# interceptor.net
KiCad netlist of a schematic drawn in EAGLE
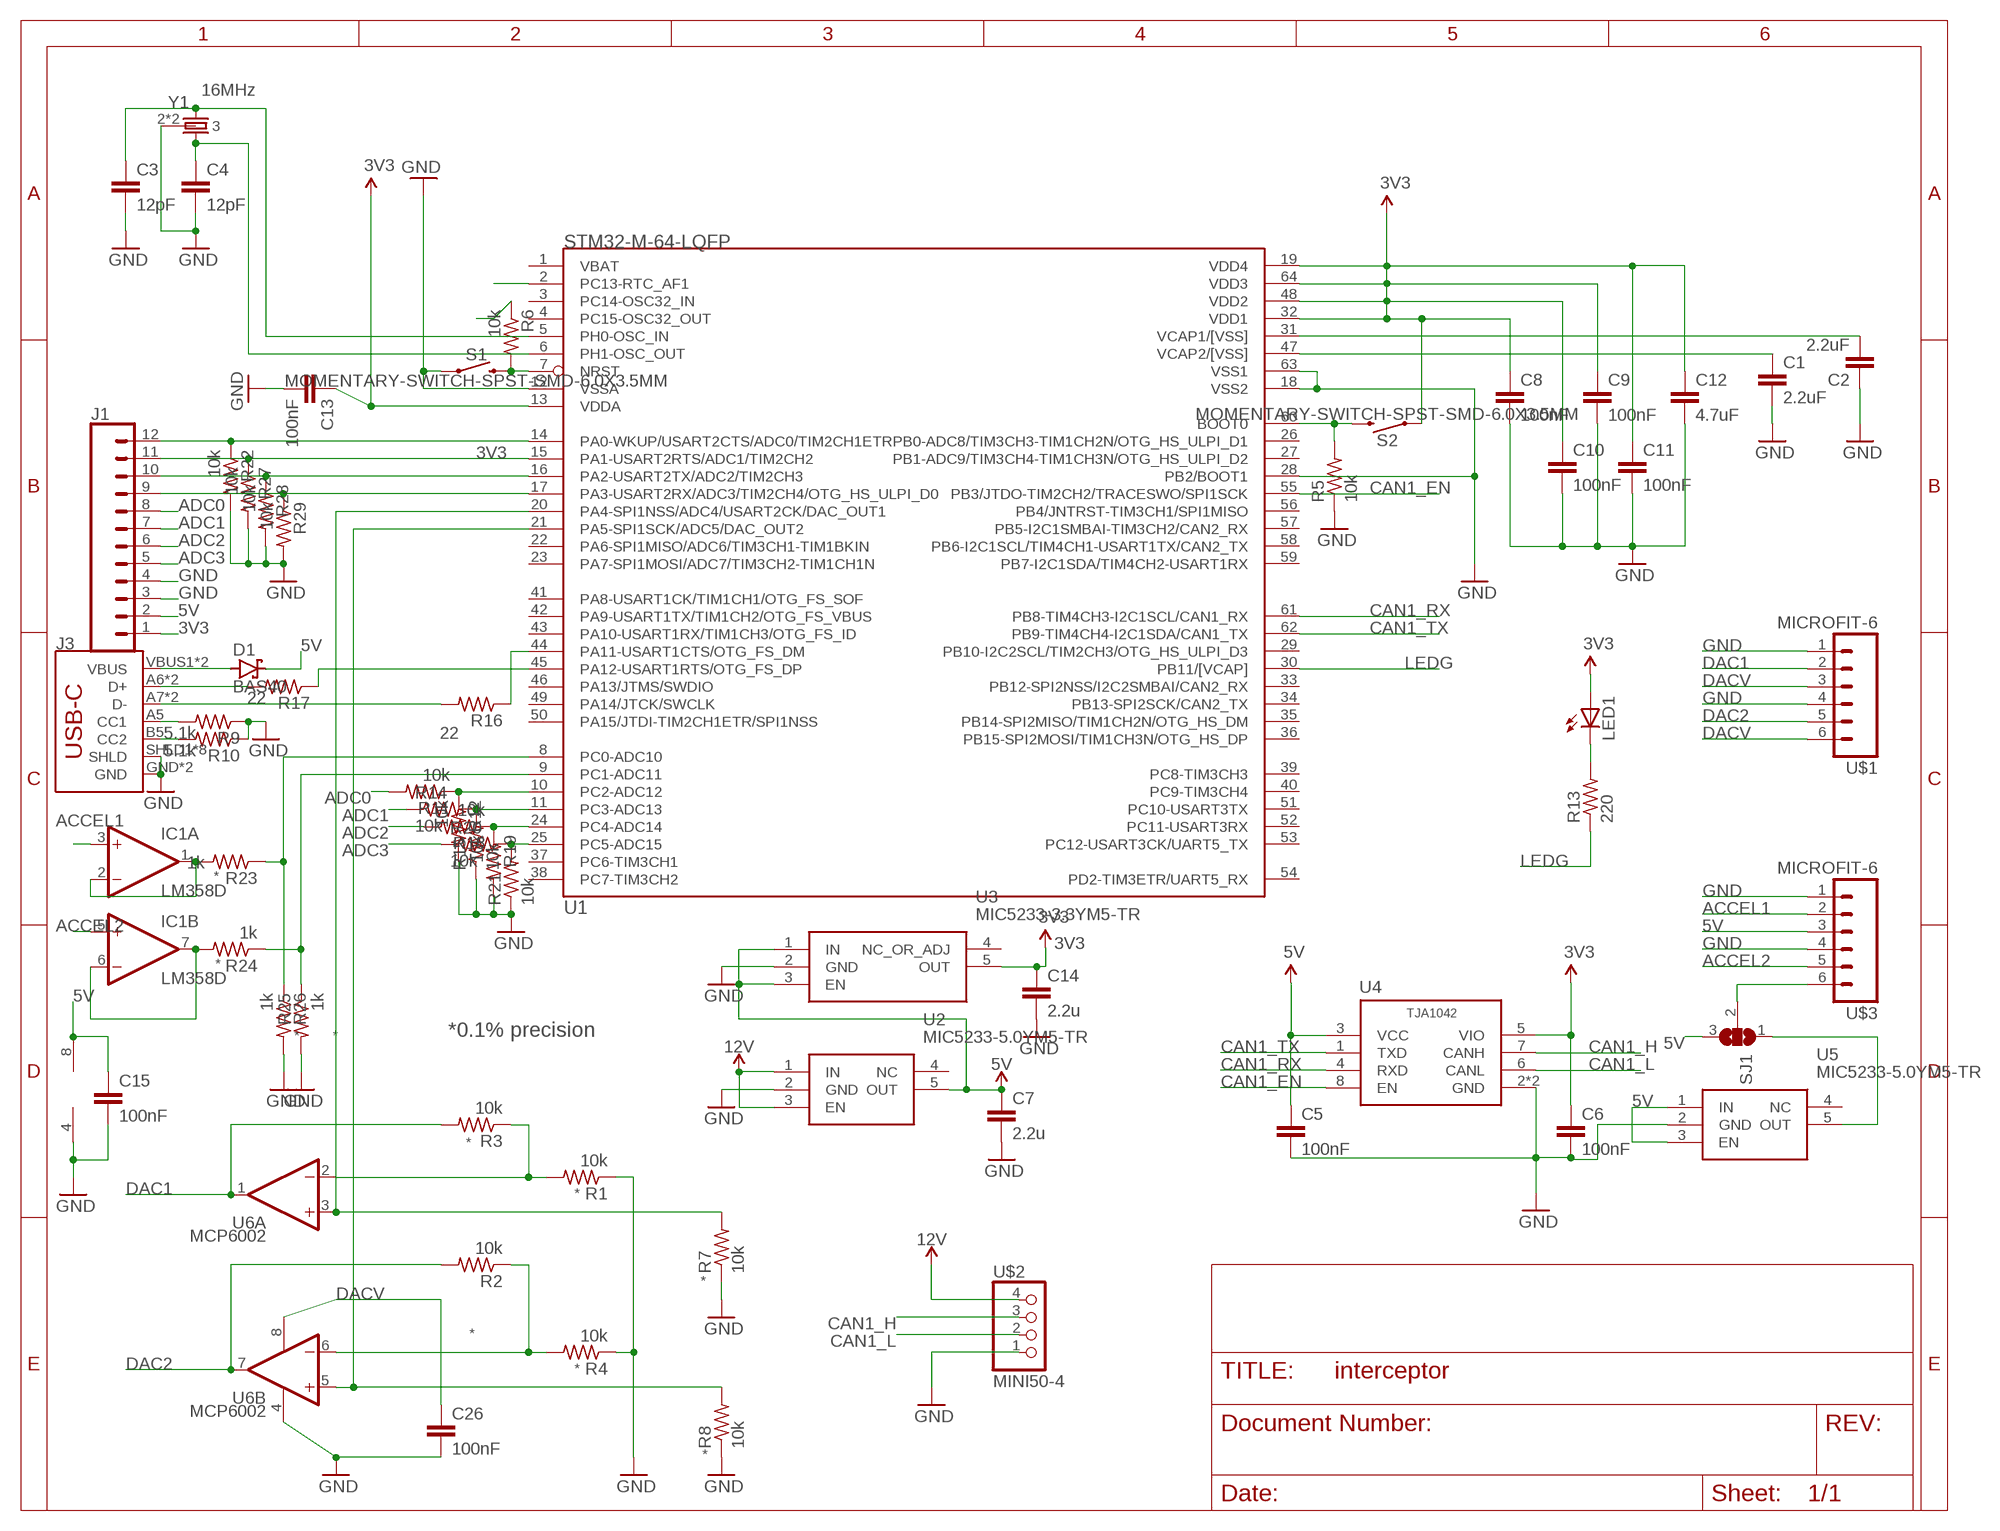
[diagram p0: schematic, sheet 1]

(export (version "E")
  (design (tool "Eeschema 10.0.6"))
  (components
    (comp (ref "C1")
      (value "2.2uF")
      (footprint "eagle-import:0603-C")
      (libsource (lib "eagle-import") (part "C0603"))
    )
    (comp (ref "C2")
      (value "2.2uF")
      (footprint "eagle-import:0603-C")
      (libsource (lib "eagle-import") (part "C0603"))
    )
    (comp (ref "C3")
      (value "12pF")
      (footprint "eagle-import:0603-C")
      (libsource (lib "eagle-import") (part "C0603"))
    )
    (comp (ref "C4")
      (value "12pF")
      (footprint "eagle-import:0603-C")
      (libsource (lib "eagle-import") (part "C0603"))
    )
    (comp (ref "C5")
      (value "100nF")
      (footprint "eagle-import:0603-C")
      (libsource (lib "eagle-import") (part "C0603"))
    )
    (comp (ref "C6")
      (value "100nF")
      (footprint "eagle-import:0603-C")
      (libsource (lib "eagle-import") (part "C0603"))
    )
    (comp (ref "C7")
      (value "2.2u")
      (footprint "eagle-import:C0603")
      (libsource (lib "eagle-import") (part "C-EUC0603"))
    )
    (comp (ref "C8")
      (value "100nF")
      (footprint "eagle-import:0603-C")
      (libsource (lib "eagle-import") (part "C0603"))
    )
    (comp (ref "C9")
      (value "100nF")
      (footprint "eagle-import:0603-C")
      (libsource (lib "eagle-import") (part "C0603"))
    )
    (comp (ref "C10")
      (value "100nF")
      (footprint "eagle-import:0603-C")
      (libsource (lib "eagle-import") (part "C0603"))
    )
    (comp (ref "C11")
      (value "100nF")
      (footprint "eagle-import:0603-C")
      (libsource (lib "eagle-import") (part "C0603"))
    )
    (comp (ref "C12")
      (value "4.7uF")
      (footprint "eagle-import:0603-C")
      (libsource (lib "eagle-import") (part "C0603"))
    )
    (comp (ref "C13")
      (value "100nF")
      (footprint "eagle-import:0603-C")
      (libsource (lib "eagle-import") (part "C0603"))
    )
    (comp (ref "C14")
      (value "2.2u")
      (footprint "eagle-import:C0603")
      (libsource (lib "eagle-import") (part "C-EUC0603"))
    )
    (comp (ref "C15")
      (value "100nF")
      (footprint "eagle-import:0603-C")
      (libsource (lib "eagle-import") (part "C0603"))
    )
    (comp (ref "C26")
      (value "100nF")
      (footprint "eagle-import:0603-C")
      (libsource (lib "eagle-import") (part "C0603"))
    )
    (comp (ref "D1")
      (value "BAS40")
      (footprint "eagle-import:SOT23")
      (libsource (lib "eagle-import") (part "BAS40"))
    )
    (comp (ref "IC1")
      (value "LM358D")
      (footprint "eagle-import:SO08")
      (libsource (lib "eagle-import") (part "LM358D"))
    )
    (comp (ref "J1")
      (value "CONN_12")
      (footprint "eagle-import:1X12")
      (libsource (lib "eagle-import") (part "CONN_12"))
    )
    (comp (ref "J3")
      (value "USB-C-BREAKOUT_SPARKFUN-CONNECTORS_USB_C16PIN")
      (footprint "eagle-import:USB-C-BREAKOUT_SPARKFUN-CONNECTORS_USB-C-16P")
      (libsource (lib "eagle-import") (part "USB-C-BREAKOUT_SPARKFUN-CONNECTORS_USB_C16PIN"))
    )
    (comp (ref "LED1")
      (value "LEDCHIPLED_0805")
      (footprint "eagle-import:CHIPLED_0805")
      (libsource (lib "eagle-import") (part "LEDCHIPLED_0805"))
    )
    (comp (ref "R1")
      (value "10k")
      (footprint "eagle-import:0402-R")
      (libsource (lib "eagle-import") (part "R0402"))
    )
    (comp (ref "R2")
      (value "10k")
      (footprint "eagle-import:0402-R")
      (libsource (lib "eagle-import") (part "R0402"))
    )
    (comp (ref "R3")
      (value "10k")
      (footprint "eagle-import:0402-R")
      (libsource (lib "eagle-import") (part "R0402"))
    )
    (comp (ref "R4")
      (value "10k")
      (footprint "eagle-import:0402-R")
      (libsource (lib "eagle-import") (part "R0402"))
    )
    (comp (ref "R5")
      (value "10k")
      (footprint "eagle-import:0402-R")
      (libsource (lib "eagle-import") (part "R0402"))
    )
    (comp (ref "R6")
      (value "10k")
      (footprint "eagle-import:0402-R")
      (libsource (lib "eagle-import") (part "R0402"))
    )
    (comp (ref "R7")
      (value "10k")
      (footprint "eagle-import:0402-R")
      (libsource (lib "eagle-import") (part "R0402"))
    )
    (comp (ref "R8")
      (value "10k")
      (footprint "eagle-import:0402-R")
      (libsource (lib "eagle-import") (part "R0402"))
    )
    (comp (ref "R9")
      (value "5.1k")
      (footprint "eagle-import:0402-R")
      (libsource (lib "eagle-import") (part "R0402"))
    )
    (comp (ref "R10")
      (value "5.1k")
      (footprint "eagle-import:0402-R")
      (libsource (lib "eagle-import") (part "R0402"))
    )
    (comp (ref "R11")
      (value "10k")
      (footprint "eagle-import:0402-R")
      (libsource (lib "eagle-import") (part "R0402"))
    )
    (comp (ref "R12")
      (value "10k")
      (footprint "eagle-import:0402-R")
      (libsource (lib "eagle-import") (part "R0402"))
    )
    (comp (ref "R13")
      (value "220")
      (footprint "eagle-import:0402-R")
      (libsource (lib "eagle-import") (part "R0402"))
    )
    (comp (ref "R14")
      (value "10k")
      (footprint "eagle-import:0402-R")
      (libsource (lib "eagle-import") (part "R0402"))
    )
    (comp (ref "R15")
      (value "10k")
      (footprint "eagle-import:0402-R")
      (libsource (lib "eagle-import") (part "R0402"))
    )
    (comp (ref "R16")
      (value "22")
      (footprint "eagle-import:0402-R")
      (libsource (lib "eagle-import") (part "R0402"))
    )
    (comp (ref "R17")
      (value "22")
      (footprint "eagle-import:0402-R")
      (libsource (lib "eagle-import") (part "R0402"))
    )
    (comp (ref "R18")
      (value "10k")
      (footprint "eagle-import:0402-R")
      (libsource (lib "eagle-import") (part "R0402"))
    )
    (comp (ref "R19")
      (value "10k")
      (footprint "eagle-import:0402-R")
      (libsource (lib "eagle-import") (part "R0402"))
    )
    (comp (ref "R20")
      (value "10k")
      (footprint "eagle-import:0402-R")
      (libsource (lib "eagle-import") (part "R0402"))
    )
    (comp (ref "R21")
      (value "10k")
      (footprint "eagle-import:0402-R")
      (libsource (lib "eagle-import") (part "R0402"))
    )
    (comp (ref "R22")
      (value "10k")
      (footprint "eagle-import:0402-R")
      (libsource (lib "eagle-import") (part "R0402"))
    )
    (comp (ref "R23")
      (value "1k")
      (footprint "eagle-import:0402-R")
      (libsource (lib "eagle-import") (part "R0402"))
    )
    (comp (ref "R24")
      (value "1k")
      (footprint "eagle-import:0402-R")
      (libsource (lib "eagle-import") (part "R0402"))
    )
    (comp (ref "R25")
      (value "1k")
      (footprint "eagle-import:0402-R")
      (libsource (lib "eagle-import") (part "R0402"))
    )
    (comp (ref "R26")
      (value "1k")
      (footprint "eagle-import:0402-R")
      (libsource (lib "eagle-import") (part "R0402"))
    )
    (comp (ref "R27")
      (value "10k")
      (footprint "eagle-import:0402-R")
      (libsource (lib "eagle-import") (part "R0402"))
    )
    (comp (ref "R28")
      (value "10k")
      (footprint "eagle-import:0402-R")
      (libsource (lib "eagle-import") (part "R0402"))
    )
    (comp (ref "R29")
      (value "10k")
      (footprint "eagle-import:0402-R")
      (libsource (lib "eagle-import") (part "R0402"))
    )
    (comp (ref "S1")
      (value "MOMENTARY-SWITCH-SPST-SMD-6.0X3.5MM")
      (footprint "eagle-import:TACTILE_SWITCH_SMD_6.0X3.5MM")
      (libsource (lib "eagle-import") (part "MOMENTARY-SWITCH-SPST-SMD-6.0X3.5MM"))
    )
    (comp (ref "S2")
      (value "MOMENTARY-SWITCH-SPST-SMD-6.0X3.5MM")
      (footprint "eagle-import:TACTILE_SWITCH_SMD_6.0X3.5MM")
      (libsource (lib "eagle-import") (part "MOMENTARY-SWITCH-SPST-SMD-6.0X3.5MM"))
    )
    (comp (ref "SJ1")
      (value "SJ2W")
      (footprint "eagle-import:SJ_2")
      (libsource (lib "eagle-import") (part "SJ2W"))
    )
    (comp (ref "U$1")
      (value "MICROFIT-6")
      (footprint "eagle-import:MICROFIT-6")
      (libsource (lib "eagle-import") (part "MICROFIT-6"))
    )
    (comp (ref "U$2")
      (value "MINI50-4")
      (footprint "eagle-import:MINI50")
      (libsource (lib "eagle-import") (part "MINI50-4"))
    )
    (comp (ref "U$3")
      (value "MICROFIT-6")
      (footprint "eagle-import:MICROFIT-6")
      (libsource (lib "eagle-import") (part "MICROFIT-6"))
    )
    (comp (ref "U1")
      (value "STM32-M-64-LQFP")
      (footprint "eagle-import:LQFP64")
      (libsource (lib "eagle-import") (part "STM32-M-64-LQFP"))
    )
    (comp (ref "U2")
      (value "MIC5233-5.0YM5-TR")
      (footprint "eagle-import:SOT95P280X145-5N")
      (fields (field (name "MOUSER_PART_NUMBER") "998-MIC5233-5.0YM5TR"))
      (libsource (lib "eagle-import") (part "MIC5233-5.0YM5-TR"))
    )
    (comp (ref "U3")
      (value "MIC5233-3.3YM5-TR")
      (footprint "eagle-import:SOT95P280X145-5N")
      (fields (field (name "MOUSER_PART_NUMBER") "998-MIC5233-3.3YM5TR"))
      (libsource (lib "eagle-import") (part "MIC5233-3.3YM5-TR"))
    )
    (comp (ref "U4")
      (value "TJA1042HVSON")
      (footprint "eagle-import:HVSON8")
      (libsource (lib "eagle-import") (part "TJA1042HVSON"))
    )
    (comp (ref "U5")
      (value "MIC5233-5.0YM5-TR")
      (footprint "eagle-import:SOT95P280X145-5N")
      (fields (field (name "MOUSER_PART_NUMBER") "998-MIC5233-5.0YM5TR"))
      (libsource (lib "eagle-import") (part "MIC5233-5.0YM5-TR"))
    )
    (comp (ref "U6")
      (value "MCP6002")
      (footprint "eagle-import:SO08")
      (libsource (lib "eagle-import") (part "LM358D"))
    )
    (comp (ref "Y1")
      (value "16MHz")
      (footprint "eagle-import:XTAL-3.2X2.5")
      (libsource (lib "eagle-import") (part "CRYSTAL-3.2X2.54-PIN"))
    )
  )
  (nets
    (net (code "1") (name "/ACCEL1") (class "Default")
      (node (ref "IC1") (pin "3") (pinfunction "+IN_3") (pintype "input"))
      (node (ref "U$3") (pin "2") (pinfunction "2_2") (pintype "passive"))
    )
    (net (code "2") (name "/ACCEL2") (class "Default")
      (node (ref "IC1") (pin "5") (pinfunction "+IN_5") (pintype "input"))
      (node (ref "U$3") (pin "5") (pinfunction "5_5") (pintype "passive"))
    )
    (net (code "3") (name "/ADC0") (class "Default")
      (node (ref "J1") (pin "8") (pinfunction "8_8") (pintype "passive"))
      (node (ref "R11") (pin "2") (pinfunction "2_2") (pintype "passive"))
    )
    (net (code "4") (name "/ADC1") (class "Default")
      (node (ref "J1") (pin "7") (pinfunction "7_7") (pintype "passive"))
      (node (ref "R14") (pin "1") (pinfunction "1_1") (pintype "passive"))
    )
    (net (code "5") (name "/ADC2") (class "Default")
      (node (ref "J1") (pin "6") (pinfunction "6_6") (pintype "passive"))
      (node (ref "R18") (pin "2") (pinfunction "2_2") (pintype "passive"))
    )
    (net (code "6") (name "/ADC3") (class "Default")
      (node (ref "J1") (pin "5") (pinfunction "5_5") (pintype "passive"))
      (node (ref "R20") (pin "1") (pinfunction "1_1") (pintype "passive"))
    )
    (net (code "7") (name "/CAN1_EN") (class "Default")
      (node (ref "U1") (pin "55") (pinfunction "PB3/JTDO-TIM2CH2/TRACESWO/SPI1SCK_55") (pintype "bidirectional"))
      (node (ref "U4") (pin "8") (pinfunction "EN_8") (pintype "bidirectional"))
    )
    (net (code "8") (name "/CAN1_H") (class "Default")
      (node (ref "U$2") (pin "3") (pinfunction "2_3") (pintype "passive"))
      (node (ref "U4") (pin "7") (pinfunction "CANH_7") (pintype "bidirectional"))
    )
    (net (code "9") (name "/CAN1_L") (class "Default")
      (node (ref "U$2") (pin "2") (pinfunction "3_2") (pintype "passive"))
      (node (ref "U4") (pin "6") (pinfunction "CANL_6") (pintype "bidirectional"))
    )
    (net (code "10") (name "/CAN1_RX") (class "Default")
      (node (ref "U1") (pin "61") (pinfunction "PB8-TIM4CH3-I2C1SCL/CAN1_RX_61") (pintype "bidirectional"))
      (node (ref "U4") (pin "4") (pinfunction "RXD_4") (pintype "bidirectional"))
    )
    (net (code "11") (name "/CAN1_TX") (class "Default")
      (node (ref "U1") (pin "62") (pinfunction "PB9-TIM4CH4-I2C1SDA/CAN1_TX_62") (pintype "bidirectional"))
      (node (ref "U4") (pin "1") (pinfunction "TXD_1") (pintype "bidirectional"))
    )
    (net (code "12") (name "/DAC1") (class "Default")
      (node (ref "R3") (pin "2") (pinfunction "2_2") (pintype "passive"))
      (node (ref "U$1") (pin "2") (pinfunction "2_2") (pintype "passive"))
      (node (ref "U6") (pin "1") (pinfunction "OUT_1") (pintype "output"))
    )
    (net (code "13") (name "/DAC2") (class "Default")
      (node (ref "R2") (pin "2") (pinfunction "2_2") (pintype "passive"))
      (node (ref "U$1") (pin "5") (pinfunction "5_5") (pintype "passive"))
      (node (ref "U6") (pin "7") (pinfunction "OUT_7") (pintype "output"))
    )
    (net (code "14") (name "/DACV") (class "Default")
      (node (ref "C26") (pin "1") (pinfunction "1_1") (pintype "passive"))
      (node (ref "U$1") (pin "3") (pinfunction "3_3") (pintype "passive"))
      (node (ref "U$1") (pin "6") (pinfunction "6_6") (pintype "passive"))
      (node (ref "U6") (pin "8") (pinfunction "V+_8") (pintype "power_in"))
    )
    (net (code "15") (name "/LEDG") (class "Default")
      (node (ref "R13") (pin "1") (pinfunction "1_1") (pintype "passive"))
      (node (ref "U1") (pin "30") (pinfunction "PB11/[VCAP]_30") (pintype "bidirectional"))
    )
    (net (code "16") (name "/VBAT") (class "Default")
      (node (ref "U1") (pin "1") (pinfunction "VBAT_1") (pintype "power_in"))
    )
    (net (code "17") (name "3V3") (class "Default")
      (node (ref "C10") (pin "1") (pinfunction "1_1") (pintype "passive"))
      (node (ref "C11") (pin "1") (pinfunction "1_1") (pintype "passive"))
      (node (ref "C12") (pin "1") (pinfunction "1_1") (pintype "passive"))
      (node (ref "C13") (pin "1") (pinfunction "1_1") (pintype "passive"))
      (node (ref "C14") (pin "1") (pinfunction "1_1") (pintype "passive"))
      (node (ref "C6") (pin "1") (pinfunction "1_1") (pintype "passive"))
      (node (ref "C8") (pin "1") (pinfunction "1_1") (pintype "passive"))
      (node (ref "C9") (pin "1") (pinfunction "1_1") (pintype "passive"))
      (node (ref "J1") (pin "1") (pinfunction "1_1") (pintype "passive"))
      (node (ref "LED1") (pin "A") (pinfunction "A_A") (pintype "passive"))
      (node (ref "R6") (pin "1") (pinfunction "1_1") (pintype "passive"))
      (node (ref "S2") (pin "1") (pinfunction "1_1") (pintype "passive"))
      (node (ref "U1") (pin "13") (pinfunction "VDDA_13") (pintype "power_in"))
      (node (ref "U1") (pin "19") (pinfunction "VDD4_19") (pintype "bidirectional"))
      (node (ref "U1") (pin "32") (pinfunction "VDD1_32") (pintype "power_in"))
      (node (ref "U1") (pin "48") (pinfunction "VDD2_48") (pintype "power_in"))
      (node (ref "U1") (pin "64") (pinfunction "VDD3_64") (pintype "power_in"))
      (node (ref "U3") (pin "5") (pinfunction "OUT_5") (pintype "bidirectional"))
      (node (ref "U4") (pin "5") (pinfunction "VIO_5") (pintype "bidirectional"))
    )
    (net (code "18") (name "5V") (class "Default")
      (node (ref "C15") (pin "1") (pinfunction "1_1") (pintype "passive"))
      (node (ref "C5") (pin "1") (pinfunction "1_1") (pintype "passive"))
      (node (ref "C7") (pin "1") (pinfunction "1_1") (pintype "passive"))
      (node (ref "D1") (pin "3") (pinfunction "C_3") (pintype "passive"))
      (node (ref "IC1") (pin "8") (pinfunction "V+_8") (pintype "power_in"))
      (node (ref "J1") (pin "2") (pinfunction "2_2") (pintype "passive"))
      (node (ref "SJ1") (pin "3") (pinfunction "3_3") (pintype "passive"))
      (node (ref "U$3") (pin "3") (pinfunction "3_3") (pintype "passive"))
      (node (ref "U2") (pin "5") (pinfunction "OUT_5") (pintype "bidirectional"))
      (node (ref "U3") (pin "1") (pinfunction "IN_1") (pintype "bidirectional"))
      (node (ref "U3") (pin "3") (pinfunction "EN_3") (pintype "bidirectional"))
      (node (ref "U4") (pin "3") (pinfunction "VCC_3") (pintype "bidirectional"))
      (node (ref "U5") (pin "1") (pinfunction "IN_1") (pintype "bidirectional"))
      (node (ref "U5") (pin "3") (pinfunction "EN_3") (pintype "bidirectional"))
    )
    (net (code "19") (name "12V") (class "Default")
      (node (ref "U$2") (pin "4") (pinfunction "1_4") (pintype "passive"))
      (node (ref "U2") (pin "1") (pinfunction "IN_1") (pintype "bidirectional"))
      (node (ref "U2") (pin "3") (pinfunction "EN_3") (pintype "bidirectional"))
    )
    (net (code "20") (name "GND") (class "Default")
      (node (ref "C1") (pin "2") (pinfunction "2_2") (pintype "passive"))
      (node (ref "C10") (pin "2") (pinfunction "2_2") (pintype "passive"))
      (node (ref "C11") (pin "2") (pinfunction "2_2") (pintype "passive"))
      (node (ref "C12") (pin "2") (pinfunction "2_2") (pintype "passive"))
      (node (ref "C13") (pin "2") (pinfunction "2_2") (pintype "passive"))
      (node (ref "C14") (pin "2") (pinfunction "2_2") (pintype "passive"))
      (node (ref "C15") (pin "2") (pinfunction "2_2") (pintype "passive"))
      (node (ref "C2") (pin "1") (pinfunction "1_1") (pintype "passive"))
      (node (ref "C26") (pin "2") (pinfunction "2_2") (pintype "passive"))
      (node (ref "C3") (pin "2") (pinfunction "2_2") (pintype "passive"))
      (node (ref "C4") (pin "2") (pinfunction "2_2") (pintype "passive"))
      (node (ref "C5") (pin "2") (pinfunction "2_2") (pintype "passive"))
      (node (ref "C6") (pin "2") (pinfunction "2_2") (pintype "passive"))
      (node (ref "C7") (pin "2") (pinfunction "2_2") (pintype "passive"))
      (node (ref "C8") (pin "2") (pinfunction "2_2") (pintype "passive"))
      (node (ref "C9") (pin "2") (pinfunction "2_2") (pintype "passive"))
      (node (ref "IC1") (pin "4") (pinfunction "V-_4") (pintype "power_in"))
      (node (ref "J1") (pin "3") (pinfunction "3_3") (pintype "passive"))
      (node (ref "J1") (pin "4") (pinfunction "4_4") (pintype "passive"))
      (node (ref "J3") (pin "GND") (pinfunction "GND_GND") (pintype "bidirectional"))
      (node (ref "J3") (pin "GND2") (pinfunction "GND_GND2") (pintype "bidirectional"))
      (node (ref "J3") (pin "SHLD1") (pinfunction "SHLD_SHLD1") (pintype "bidirectional"))
      (node (ref "J3") (pin "SHLD2") (pinfunction "SHLD_SHLD2") (pintype "bidirectional"))
      (node (ref "J3") (pin "SHLD3") (pinfunction "SHLD_SHLD3") (pintype "bidirectional"))
      (node (ref "J3") (pin "SHLD4") (pinfunction "SHLD_SHLD4") (pintype "bidirectional"))
      (node (ref "J3") (pin "SHLD5") (pinfunction "SHLD_SHLD5") (pintype "bidirectional"))
      (node (ref "J3") (pin "SHLD6") (pinfunction "SHLD_SHLD6") (pintype "bidirectional"))
      (node (ref "J3") (pin "SHLD7") (pinfunction "SHLD_SHLD7") (pintype "bidirectional"))
      (node (ref "J3") (pin "SHLD8") (pinfunction "SHLD_SHLD8") (pintype "bidirectional"))
      (node (ref "R1") (pin "1") (pinfunction "1_1") (pintype "passive"))
      (node (ref "R10") (pin "1") (pinfunction "1_1") (pintype "passive"))
      (node (ref "R12") (pin "2") (pinfunction "2_2") (pintype "passive"))
      (node (ref "R15") (pin "1") (pinfunction "1_1") (pintype "passive"))
      (node (ref "R19") (pin "2") (pinfunction "2_2") (pintype "passive"))
      (node (ref "R21") (pin "1") (pinfunction "1_1") (pintype "passive"))
      (node (ref "R22") (pin "2") (pinfunction "2_2") (pintype "passive"))
      (node (ref "R25") (pin "2") (pinfunction "2_2") (pintype "passive"))
      (node (ref "R26") (pin "2") (pinfunction "2_2") (pintype "passive"))
      (node (ref "R27") (pin "2") (pinfunction "2_2") (pintype "passive"))
      (node (ref "R28") (pin "2") (pinfunction "2_2") (pintype "passive"))
      (node (ref "R29") (pin "2") (pinfunction "2_2") (pintype "passive"))
      (node (ref "R4") (pin "1") (pinfunction "1_1") (pintype "passive"))
      (node (ref "R5") (pin "1") (pinfunction "1_1") (pintype "passive"))
      (node (ref "R7") (pin "1") (pinfunction "1_1") (pintype "passive"))
      (node (ref "R8") (pin "1") (pinfunction "1_1") (pintype "passive"))
      (node (ref "R9") (pin "1") (pinfunction "1_1") (pintype "passive"))
      (node (ref "S1") (pin "1") (pinfunction "1_1") (pintype "passive"))
      (node (ref "U$1") (pin "1") (pinfunction "1_1") (pintype "passive"))
      (node (ref "U$1") (pin "4") (pinfunction "4_4") (pintype "passive"))
      (node (ref "U$2") (pin "1") (pinfunction "4_1") (pintype "passive"))
      (node (ref "U$3") (pin "1") (pinfunction "1_1") (pintype "passive"))
      (node (ref "U$3") (pin "4") (pinfunction "4_4") (pintype "passive"))
      (node (ref "U1") (pin "12") (pinfunction "VSSA_12") (pintype "power_in"))
      (node (ref "U1") (pin "18") (pinfunction "VSS2_18") (pintype "bidirectional"))
      (node (ref "U1") (pin "28") (pinfunction "PB2/BOOT1_28") (pintype "bidirectional"))
      (node (ref "U1") (pin "63") (pinfunction "VSS1_63") (pintype "power_in"))
      (node (ref "U2") (pin "2") (pinfunction "GND_2") (pintype "bidirectional"))
      (node (ref "U3") (pin "2") (pinfunction "GND_2") (pintype "bidirectional"))
      (node (ref "U4") (pin "2") (pinfunction "GND_2") (pintype "bidirectional"))
      (node (ref "U4") (pin "PAD") (pinfunction "GND_PAD") (pintype "bidirectional"))
      (node (ref "U5") (pin "2") (pinfunction "GND_2") (pintype "bidirectional"))
      (node (ref "U6") (pin "4") (pinfunction "V-_4") (pintype "power_in"))
      (node (ref "Y1") (pin "2") (pinfunction "3_2") (pintype "bidirectional"))
      (node (ref "Y1") (pin "4") (pinfunction "3_4") (pintype "bidirectional"))
    )
    (net (code "21") (name "Net-(D1-A)") (class "Default")
      (node (ref "D1") (pin "1") (pinfunction "A_1") (pintype "passive"))
      (node (ref "J3") (pin "VBUS1") (pinfunction "VBUS_VBUS1") (pintype "bidirectional"))
      (node (ref "J3") (pin "VBUS2") (pinfunction "VBUS_VBUS2") (pintype "bidirectional"))
    )
    (net (code "22") (name "Net-(IC1A--IN)") (class "Default")
      (node (ref "IC1") (pin "1") (pinfunction "OUT_1") (pintype "output"))
      (node (ref "IC1") (pin "2") (pinfunction "-IN_2") (pintype "input"))
      (node (ref "R23") (pin "2") (pinfunction "2_2") (pintype "passive"))
    )
    (net (code "23") (name "Net-(IC1B--IN)") (class "Default")
      (node (ref "IC1") (pin "6") (pinfunction "-IN_6") (pintype "input"))
      (node (ref "IC1") (pin "7") (pinfunction "OUT_7") (pintype "output"))
      (node (ref "R24") (pin "2") (pinfunction "2_2") (pintype "passive"))
    )
    (net (code "24") (name "Net-(J3-CC1)") (class "Default")
      (node (ref "J3") (pin "A5") (pinfunction "CC1_A5") (pintype "bidirectional"))
      (node (ref "R9") (pin "2") (pinfunction "2_2") (pintype "passive"))
    )
    (net (code "25") (name "Net-(J3-CC2)") (class "Default")
      (node (ref "J3") (pin "B5") (pinfunction "CC2_B5") (pintype "bidirectional"))
      (node (ref "R10") (pin "2") (pinfunction "2_2") (pintype "passive"))
    )
    (net (code "26") (name "Net-(J3-D+-PadA6)") (class "Default")
      (node (ref "J3") (pin "A6") (pinfunction "D+_A6") (pintype "bidirectional"))
      (node (ref "J3") (pin "B6") (pinfunction "D+_B6") (pintype "bidirectional"))
      (node (ref "R17") (pin "2") (pinfunction "2_2") (pintype "passive"))
    )
    (net (code "27") (name "Net-(J3-D--PadA7)") (class "Default")
      (node (ref "J3") (pin "A7") (pinfunction "D-_A7") (pintype "bidirectional"))
      (node (ref "J3") (pin "B7") (pinfunction "D-_B7") (pintype "bidirectional"))
      (node (ref "R16") (pin "2") (pinfunction "2_2") (pintype "passive"))
    )
    (net (code "28") (name "Net-(LED1-PadC)") (class "Default")
      (node (ref "LED1") (pin "C") (pinfunction "C_C") (pintype "passive"))
      (node (ref "R13") (pin "2") (pinfunction "2_2") (pintype "passive"))
    )
    (net (code "29") (name "Net-(SJ1-Pad2)") (class "Default")
      (node (ref "SJ1") (pin "2") (pinfunction "2_2") (pintype "passive"))
      (node (ref "U$3") (pin "6") (pinfunction "6_6") (pintype "passive"))
    )
    (net (code "30") (name "Net-(U1-BOOT0)") (class "Default")
      (node (ref "R5") (pin "2") (pinfunction "2_2") (pintype "passive"))
      (node (ref "S2") (pin "2") (pinfunction "2_2") (pintype "passive"))
      (node (ref "U1") (pin "60") (pinfunction "BOOT0_60") (pintype "input"))
    )
    (net (code "31") (name "Net-(U1-NRST)") (class "Default")
      (node (ref "R6") (pin "2") (pinfunction "2_2") (pintype "passive"))
      (node (ref "S1") (pin "2") (pinfunction "2_2") (pintype "passive"))
      (node (ref "U1") (pin "7") (pinfunction "NRST_7") (pintype "bidirectional"))
    )
    (net (code "32") (name "Net-(U1-PA0-WKUP{slash}USART2CTS{slash}ADC0{slash}TIM2CH1ETR)") (class "Default")
      (node (ref "J1") (pin "12") (pinfunction "12_12") (pintype "passive"))
      (node (ref "R22") (pin "1") (pinfunction "1_1") (pintype "passive"))
      (node (ref "U1") (pin "14") (pinfunction "PA0-WKUP/USART2CTS/ADC0/TIM2CH1ETR_14") (pintype "bidirectional"))
    )
    (net (code "33") (name "Net-(U1-PA1-USART2RTS{slash}ADC1{slash}TIM2CH2)") (class "Default")
      (node (ref "J1") (pin "11") (pinfunction "11_11") (pintype "passive"))
      (node (ref "R27") (pin "1") (pinfunction "1_1") (pintype "passive"))
      (node (ref "U1") (pin "15") (pinfunction "PA1-USART2RTS/ADC1/TIM2CH2_15") (pintype "bidirectional"))
    )
    (net (code "34") (name "Net-(U1-PA2-USART2TX{slash}ADC2{slash}TIM2CH3)") (class "Default")
      (node (ref "J1") (pin "10") (pinfunction "10_10") (pintype "passive"))
      (node (ref "R28") (pin "1") (pinfunction "1_1") (pintype "passive"))
      (node (ref "U1") (pin "16") (pinfunction "PA2-USART2TX/ADC2/TIM2CH3_16") (pintype "bidirectional"))
    )
    (net (code "35") (name "Net-(U1-PA3-USART2RX{slash}ADC3{slash}TIM2CH4{slash}OTG_HS_ULPI_D0)") (class "Default")
      (node (ref "J1") (pin "9") (pinfunction "9_9") (pintype "passive"))
      (node (ref "R29") (pin "1") (pinfunction "1_1") (pintype "passive"))
      (node (ref "U1") (pin "17") (pinfunction "PA3-USART2RX/ADC3/TIM2CH4/OTG_HS_ULPI_D0_17") (pintype "bidirectional"))
    )
    (net (code "36") (name "Net-(U1-PA4-SPI1NSS{slash}ADC4{slash}USART2CK{slash}DAC_OUT1)") (class "Default")
      (node (ref "R7") (pin "2") (pinfunction "2_2") (pintype "passive"))
      (node (ref "U1") (pin "20") (pinfunction "PA4-SPI1NSS/ADC4/USART2CK/DAC_OUT1_20") (pintype "bidirectional"))
      (node (ref "U6") (pin "3") (pinfunction "+IN_3") (pintype "input"))
    )
    (net (code "37") (name "Net-(U1-PA5-SPI1SCK{slash}ADC5{slash}DAC_OUT2)") (class "Default")
      (node (ref "R8") (pin "2") (pinfunction "2_2") (pintype "passive"))
      (node (ref "U1") (pin "21") (pinfunction "PA5-SPI1SCK/ADC5/DAC_OUT2_21") (pintype "bidirectional"))
      (node (ref "U6") (pin "5") (pinfunction "+IN_5") (pintype "input"))
    )
    (net (code "38") (name "Net-(U1-PA11-USART1CTS{slash}OTG_FS_DM)") (class "Default")
      (node (ref "R16") (pin "1") (pinfunction "1_1") (pintype "passive"))
      (node (ref "U1") (pin "44") (pinfunction "PA11-USART1CTS/OTG_FS_DM_44") (pintype "bidirectional"))
    )
    (net (code "39") (name "Net-(U1-PA12-USART1RTS{slash}OTG_FS_DP)") (class "Default")
      (node (ref "R17") (pin "1") (pinfunction "1_1") (pintype "passive"))
      (node (ref "U1") (pin "45") (pinfunction "PA12-USART1RTS/OTG_FS_DP_45") (pintype "bidirectional"))
    )
    (net (code "40") (name "Net-(U1-PC0-ADC10)") (class "Default")
      (node (ref "R23") (pin "1") (pinfunction "1_1") (pintype "passive"))
      (node (ref "R26") (pin "1") (pinfunction "1_1") (pintype "passive"))
      (node (ref "U1") (pin "8") (pinfunction "PC0-ADC10_8") (pintype "bidirectional"))
    )
    (net (code "41") (name "Net-(U1-PC1-ADC11)") (class "Default")
      (node (ref "R24") (pin "1") (pinfunction "1_1") (pintype "passive"))
      (node (ref "R25") (pin "1") (pinfunction "1_1") (pintype "passive"))
      (node (ref "U1") (pin "9") (pinfunction "PC1-ADC11_9") (pintype "bidirectional"))
    )
    (net (code "42") (name "Net-(U1-PC2-ADC12)") (class "Default")
      (node (ref "R11") (pin "1") (pinfunction "1_1") (pintype "passive"))
      (node (ref "R12") (pin "1") (pinfunction "1_1") (pintype "passive"))
      (node (ref "U1") (pin "10") (pinfunction "PC2-ADC12_10") (pintype "bidirectional"))
    )
    (net (code "43") (name "Net-(U1-PC3-ADC13)") (class "Default")
      (node (ref "R14") (pin "2") (pinfunction "2_2") (pintype "passive"))
      (node (ref "R15") (pin "2") (pinfunction "2_2") (pintype "passive"))
      (node (ref "U1") (pin "11") (pinfunction "PC3-ADC13_11") (pintype "bidirectional"))
    )
    (net (code "44") (name "Net-(U1-PC4-ADC14)") (class "Default")
      (node (ref "R18") (pin "1") (pinfunction "1_1") (pintype "passive"))
      (node (ref "R19") (pin "1") (pinfunction "1_1") (pintype "passive"))
      (node (ref "U1") (pin "24") (pinfunction "PC4-ADC14_24") (pintype "bidirectional"))
    )
    (net (code "45") (name "Net-(U1-PC5-ADC15)") (class "Default")
      (node (ref "R20") (pin "2") (pinfunction "2_2") (pintype "passive"))
      (node (ref "R21") (pin "2") (pinfunction "2_2") (pintype "passive"))
      (node (ref "U1") (pin "25") (pinfunction "PC5-ADC15_25") (pintype "bidirectional"))
    )
    (net (code "46") (name "Net-(U1-PH0-OSC_IN)") (class "Default")
      (node (ref "C3") (pin "1") (pinfunction "1_1") (pintype "passive"))
      (node (ref "U1") (pin "5") (pinfunction "PH0-OSC_IN_5") (pintype "input"))
      (node (ref "Y1") (pin "1") (pinfunction "1_1") (pintype "passive"))
    )
    (net (code "47") (name "Net-(U1-PH1-OSC_OUT)") (class "Default")
      (node (ref "C4") (pin "1") (pinfunction "1_1") (pintype "passive"))
      (node (ref "U1") (pin "6") (pinfunction "PH1-OSC_OUT_6") (pintype "output"))
      (node (ref "Y1") (pin "3") (pinfunction "2_3") (pintype "passive"))
    )
    (net (code "48") (name "Net-(U1-VCAP1{slash}[VSS])") (class "Default")
      (node (ref "C2") (pin "2") (pinfunction "2_2") (pintype "passive"))
      (node (ref "U1") (pin "31") (pinfunction "VCAP1/[VSS]_31") (pintype "power_in"))
    )
    (net (code "49") (name "Net-(U1-VCAP2{slash}[VSS])") (class "Default")
      (node (ref "C1") (pin "1") (pinfunction "1_1") (pintype "passive"))
      (node (ref "U1") (pin "47") (pinfunction "VCAP2/[VSS]_47") (pintype "power_in"))
    )
    (net (code "50") (name "Net-(U5-OUT)") (class "Default")
      (node (ref "SJ1") (pin "1") (pinfunction "1_1") (pintype "passive"))
      (node (ref "U5") (pin "5") (pinfunction "OUT_5") (pintype "bidirectional"))
    )
    (net (code "51") (name "Net-(U6A--IN)") (class "Default")
      (node (ref "R1") (pin "2") (pinfunction "2_2") (pintype "passive"))
      (node (ref "R3") (pin "1") (pinfunction "1_1") (pintype "passive"))
      (node (ref "U6") (pin "2") (pinfunction "-IN_2") (pintype "input"))
    )
    (net (code "52") (name "Net-(U6B--IN)") (class "Default")
      (node (ref "R2") (pin "1") (pinfunction "1_1") (pintype "passive"))
      (node (ref "R4") (pin "2") (pinfunction "2_2") (pintype "passive"))
      (node (ref "U6") (pin "6") (pinfunction "-IN_6") (pintype "input"))
    )
    (net (code "53") (name "unconnected-(U1-PA6-SPI1MISO{slash}ADC6{slash}TIM3CH1-TIM1BKIN-Pad22)") (class "Default")
      (node (ref "U1") (pin "22") (pinfunction "PA6-SPI1MISO/ADC6/TIM3CH1-TIM1BKIN_22") (pintype "bidirectional"))
    )
    (net (code "54") (name "unconnected-(U1-PA7-SPI1MOSI{slash}ADC7{slash}TIM3CH2-TIM1CH1N-Pad23)") (class "Default")
      (node (ref "U1") (pin "23") (pinfunction "PA7-SPI1MOSI/ADC7/TIM3CH2-TIM1CH1N_23") (pintype "bidirectional"))
    )
    (net (code "55") (name "unconnected-(U1-PA8-USART1CK{slash}TIM1CH1{slash}OTG_FS_SOF-Pad41)") (class "Default")
      (node (ref "U1") (pin "41") (pinfunction "PA8-USART1CK/TIM1CH1/OTG_FS_SOF_41") (pintype "bidirectional"))
    )
    (net (code "56") (name "unconnected-(U1-PA9-USART1TX{slash}TIM1CH2{slash}OTG_FS_VBUS-Pad42)") (class "Default")
      (node (ref "U1") (pin "42") (pinfunction "PA9-USART1TX/TIM1CH2/OTG_FS_VBUS_42") (pintype "bidirectional"))
    )
    (net (code "57") (name "unconnected-(U1-PA10-USART1RX{slash}TIM1CH3{slash}OTG_FS_ID-Pad43)") (class "Default")
      (node (ref "U1") (pin "43") (pinfunction "PA10-USART1RX/TIM1CH3/OTG_FS_ID_43") (pintype "bidirectional"))
    )
    (net (code "58") (name "unconnected-(U1-PA13{slash}JTMS{slash}SWDIO-Pad46)") (class "Default")
      (node (ref "U1") (pin "46") (pinfunction "PA13/JTMS/SWDIO_46") (pintype "bidirectional"))
    )
    (net (code "59") (name "unconnected-(U1-PA14{slash}JTCK{slash}SWCLK-Pad49)") (class "Default")
      (node (ref "U1") (pin "49") (pinfunction "PA14/JTCK/SWCLK_49") (pintype "bidirectional"))
    )
    (net (code "60") (name "unconnected-(U1-PA15{slash}JTDI-TIM2CH1ETR{slash}SPI1NSS-Pad50)") (class "Default")
      (node (ref "U1") (pin "50") (pinfunction "PA15/JTDI-TIM2CH1ETR/SPI1NSS_50") (pintype "bidirectional"))
    )
    (net (code "61") (name "unconnected-(U1-PB0-ADC8{slash}TIM3CH3-TIM1CH2N{slash}OTG_HS_ULPI_D1-Pad26)") (class "Default")
      (node (ref "U1") (pin "26") (pinfunction "PB0-ADC8/TIM3CH3-TIM1CH2N/OTG_HS_ULPI_D1_26") (pintype "bidirectional"))
    )
    (net (code "62") (name "unconnected-(U1-PB1-ADC9{slash}TIM3CH4-TIM1CH3N{slash}OTG_HS_ULPI_D2-Pad27)") (class "Default")
      (node (ref "U1") (pin "27") (pinfunction "PB1-ADC9/TIM3CH4-TIM1CH3N/OTG_HS_ULPI_D2_27") (pintype "bidirectional"))
    )
    (net (code "63") (name "unconnected-(U1-PB4{slash}JNTRST-TIM3CH1{slash}SPI1MISO-Pad56)") (class "Default")
      (node (ref "U1") (pin "56") (pinfunction "PB4/JNTRST-TIM3CH1/SPI1MISO_56") (pintype "bidirectional"))
    )
    (net (code "64") (name "unconnected-(U1-PB5-I2C1SMBAI-TIM3CH2{slash}CAN2_RX-Pad57)") (class "Default")
      (node (ref "U1") (pin "57") (pinfunction "PB5-I2C1SMBAI-TIM3CH2/CAN2_RX_57") (pintype "bidirectional"))
    )
    (net (code "65") (name "unconnected-(U1-PB6-I2C1SCL{slash}TIM4CH1-USART1TX{slash}CAN2_TX-Pad58)") (class "Default")
      (node (ref "U1") (pin "58") (pinfunction "PB6-I2C1SCL/TIM4CH1-USART1TX/CAN2_TX_58") (pintype "bidirectional"))
    )
    (net (code "66") (name "unconnected-(U1-PB7-I2C1SDA{slash}TIM4CH2-USART1RX-Pad59)") (class "Default")
      (node (ref "U1") (pin "59") (pinfunction "PB7-I2C1SDA/TIM4CH2-USART1RX_59") (pintype "bidirectional"))
    )
    (net (code "67") (name "unconnected-(U1-PB10-I2C2SCL{slash}TIM2CH3{slash}OTG_HS_ULPI_D3-Pad29)") (class "Default")
      (node (ref "U1") (pin "29") (pinfunction "PB10-I2C2SCL/TIM2CH3/OTG_HS_ULPI_D3_29") (pintype "bidirectional"))
    )
    (net (code "68") (name "unconnected-(U1-PB12-SPI2NSS{slash}I2C2SMBAI{slash}CAN2_RX-Pad33)") (class "Default")
      (node (ref "U1") (pin "33") (pinfunction "PB12-SPI2NSS/I2C2SMBAI/CAN2_RX_33") (pintype "bidirectional"))
    )
    (net (code "69") (name "unconnected-(U1-PB13-SPI2SCK{slash}CAN2_TX-Pad34)") (class "Default")
      (node (ref "U1") (pin "34") (pinfunction "PB13-SPI2SCK/CAN2_TX_34") (pintype "bidirectional"))
    )
    (net (code "70") (name "unconnected-(U1-PB14-SPI2MISO{slash}TIM1CH2N{slash}OTG_HS_DM-Pad35)") (class "Default")
      (node (ref "U1") (pin "35") (pinfunction "PB14-SPI2MISO/TIM1CH2N/OTG_HS_DM_35") (pintype "bidirectional"))
    )
    (net (code "71") (name "unconnected-(U1-PB15-SPI2MOSI{slash}TIM1CH3N{slash}OTG_HS_DP-Pad36)") (class "Default")
      (node (ref "U1") (pin "36") (pinfunction "PB15-SPI2MOSI/TIM1CH3N/OTG_HS_DP_36") (pintype "bidirectional"))
    )
    (net (code "72") (name "unconnected-(U1-PC6-TIM3CH1-Pad37)") (class "Default")
      (node (ref "U1") (pin "37") (pinfunction "PC6-TIM3CH1_37") (pintype "bidirectional"))
    )
    (net (code "73") (name "unconnected-(U1-PC7-TIM3CH2-Pad38)") (class "Default")
      (node (ref "U1") (pin "38") (pinfunction "PC7-TIM3CH2_38") (pintype "bidirectional"))
    )
    (net (code "74") (name "unconnected-(U1-PC8-TIM3CH3-Pad39)") (class "Default")
      (node (ref "U1") (pin "39") (pinfunction "PC8-TIM3CH3_39") (pintype "bidirectional"))
    )
    (net (code "75") (name "unconnected-(U1-PC9-TIM3CH4-Pad40)") (class "Default")
      (node (ref "U1") (pin "40") (pinfunction "PC9-TIM3CH4_40") (pintype "bidirectional"))
    )
    (net (code "76") (name "unconnected-(U1-PC10-USART3TX-Pad51)") (class "Default")
      (node (ref "U1") (pin "51") (pinfunction "PC10-USART3TX_51") (pintype "bidirectional"))
    )
    (net (code "77") (name "unconnected-(U1-PC11-USART3RX-Pad52)") (class "Default")
      (node (ref "U1") (pin "52") (pinfunction "PC11-USART3RX_52") (pintype "bidirectional"))
    )
    (net (code "78") (name "unconnected-(U1-PC12-USART3CK{slash}UART5_TX-Pad53)") (class "Default")
      (node (ref "U1") (pin "53") (pinfunction "PC12-USART3CK/UART5_TX_53") (pintype "bidirectional"))
    )
    (net (code "79") (name "unconnected-(U1-PC13-RTC_AF1-Pad2)") (class "Default")
      (node (ref "U1") (pin "2") (pinfunction "PC13-RTC_AF1_2") (pintype "bidirectional"))
    )
    (net (code "80") (name "unconnected-(U1-PC14-OSC32_IN-Pad3)") (class "Default")
      (node (ref "U1") (pin "3") (pinfunction "PC14-OSC32_IN_3") (pintype "bidirectional"))
    )
    (net (code "81") (name "unconnected-(U1-PC15-OSC32_OUT-Pad4)") (class "Default")
      (node (ref "U1") (pin "4") (pinfunction "PC15-OSC32_OUT_4") (pintype "bidirectional"))
    )
    (net (code "82") (name "unconnected-(U1-PD2-TIM3ETR{slash}UART5_RX-Pad54)") (class "Default")
      (node (ref "U1") (pin "54") (pinfunction "PD2-TIM3ETR/UART5_RX_54") (pintype "bidirectional"))
    )
    (net (code "83") (name "unconnected-(U2-NC-Pad4)") (class "Default")
      (node (ref "U2") (pin "4") (pinfunction "NC_4") (pintype "no_connect"))
    )
    (net (code "84") (name "unconnected-(U3-NC_OR_ADJ-Pad4)") (class "Default")
      (node (ref "U3") (pin "4") (pinfunction "NC_OR_ADJ_4") (pintype "bidirectional"))
    )
    (net (code "85") (name "unconnected-(U5-NC-Pad4)") (class "Default")
      (node (ref "U5") (pin "4") (pinfunction "NC_4") (pintype "no_connect"))
    )
  )
)
